# XOR_gate.net
KiCad netlist of a schematic drawn in EAGLE
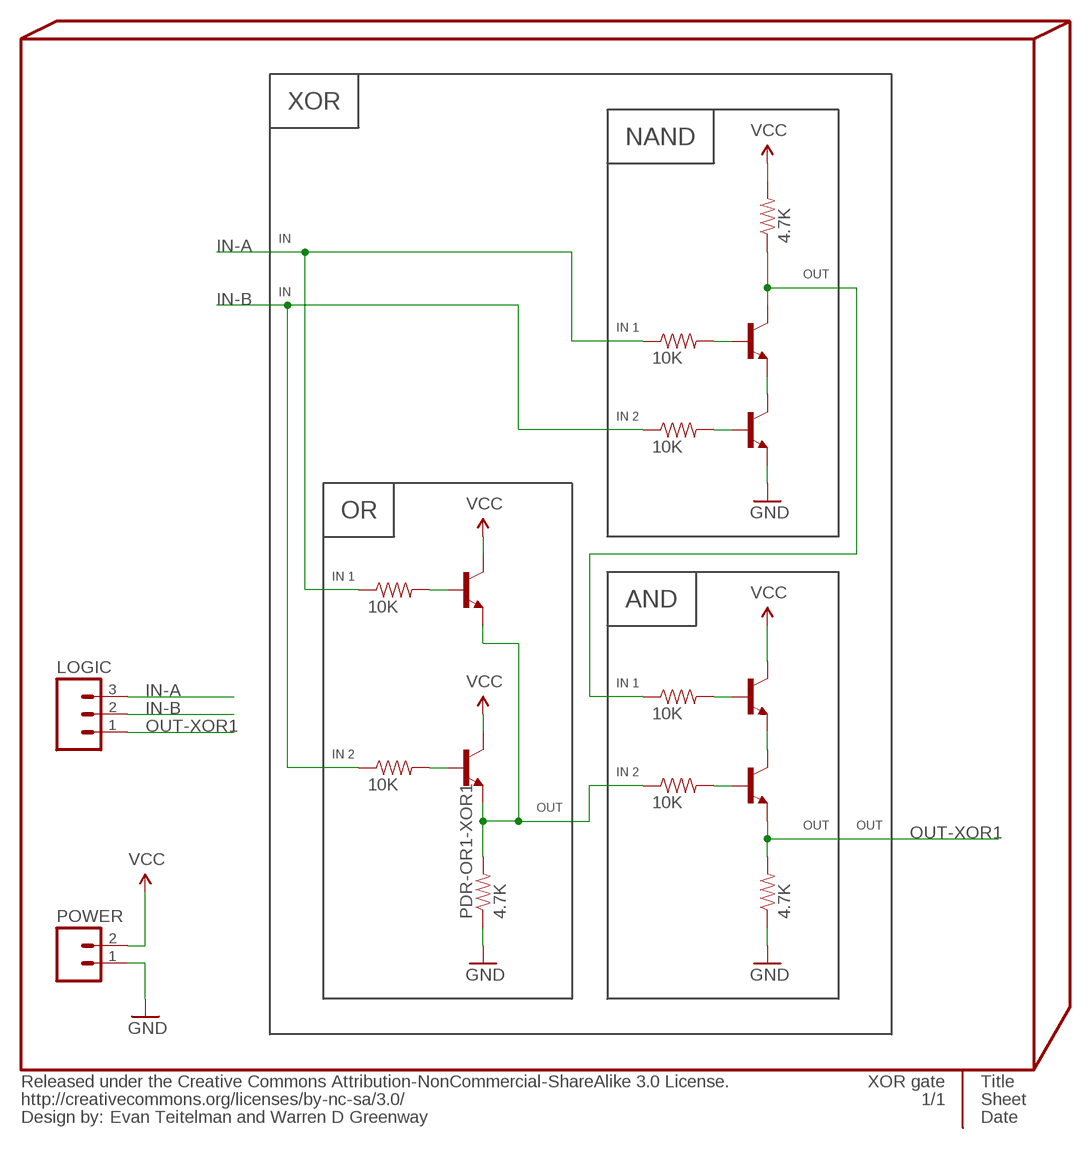
[diagram p0: schematic, sheet 1]

(export (version "E")
  (design (tool "Eeschema 10.0.6"))
  (components
    (comp (ref "INFO4")
      (value "Evan Teitelman and Warren D Greenway")
      (footprint "eagle-import:%CC-NC-SA")
      (libsource (lib "eagle-import") (part "%CC-NC-SA"))
    )
    (comp (ref "LOGIC")
      (value "M03PTH")
      (footprint "eagle-import:1X03")
      (libsource (lib "eagle-import") (part "M03PTH"))
    )
    (comp (ref "PDR-AND1-XOR1")
      (value "4.7K")
      (footprint "eagle-import:0402-RES")
      (libsource (lib "eagle-import") (part "RESISTOR0402-RES"))
    )
    (comp (ref "PDR-OR1-XOR1")
      (value "4.7K")
      (footprint "eagle-import:0402-RES")
      (libsource (lib "eagle-import") (part "RESISTOR0402-RES"))
    )
    (comp (ref "POWER")
      (value "M02PTH")
      (footprint "eagle-import:1X02")
      (libsource (lib "eagle-import") (part "M02PTH"))
    )
    (comp (ref "PUR-NAND1-XOR1")
      (value "4.7K")
      (footprint "eagle-import:0402-RES")
      (libsource (lib "eagle-import") (part "RESISTOR0402-RES"))
    )
    (comp (ref "Q1-AND1-XOR1")
      (value "TRANSISTOR_NPNSOT23")
      (footprint "eagle-import:SOT23")
      (libsource (lib "eagle-import") (part "TRANSISTOR_NPNSOT23"))
    )
    (comp (ref "Q1-NAND1-XOR1")
      (value "TRANSISTOR_NPNSOT23")
      (footprint "eagle-import:SOT23")
      (libsource (lib "eagle-import") (part "TRANSISTOR_NPNSOT23"))
    )
    (comp (ref "Q1-OR1-XOR1")
      (value "TRANSISTOR_NPNSOT23")
      (footprint "eagle-import:SOT23")
      (libsource (lib "eagle-import") (part "TRANSISTOR_NPNSOT23"))
    )
    (comp (ref "Q2-AND1-XOR1")
      (value "TRANSISTOR_NPNSOT23")
      (footprint "eagle-import:SOT23")
      (libsource (lib "eagle-import") (part "TRANSISTOR_NPNSOT23"))
    )
    (comp (ref "Q2-NAND1-XOR1")
      (value "TRANSISTOR_NPNSOT23")
      (footprint "eagle-import:SOT23")
      (libsource (lib "eagle-import") (part "TRANSISTOR_NPNSOT23"))
    )
    (comp (ref "Q2-OR1-XOR1")
      (value "TRANSISTOR_NPNSOT23")
      (footprint "eagle-import:SOT23")
      (libsource (lib "eagle-import") (part "TRANSISTOR_NPNSOT23"))
    )
    (comp (ref "R1-AND1-XOR1")
      (value "10K")
      (footprint "eagle-import:0402-RES")
      (libsource (lib "eagle-import") (part "RESISTOR0402-RES"))
    )
    (comp (ref "R1-NAND1-XOR1")
      (value "10K")
      (footprint "eagle-import:0402-RES")
      (libsource (lib "eagle-import") (part "RESISTOR0402-RES"))
    )
    (comp (ref "R1-OR1-XOR1")
      (value "10K")
      (footprint "eagle-import:0402-RES")
      (libsource (lib "eagle-import") (part "RESISTOR0402-RES"))
    )
    (comp (ref "R2-AND1-XOR1")
      (value "10K")
      (footprint "eagle-import:0402-RES")
      (libsource (lib "eagle-import") (part "RESISTOR0402-RES"))
    )
    (comp (ref "R2-NAND1-XOR1")
      (value "10K")
      (footprint "eagle-import:0402-RES")
      (libsource (lib "eagle-import") (part "RESISTOR0402-RES"))
    )
    (comp (ref "R2-OR1-XOR1")
      (value "10K")
      (footprint "eagle-import:0402-RES")
      (libsource (lib "eagle-import") (part "RESISTOR0402-RES"))
    )
  )
  (nets
    (net (code "1") (name "/IN-A") (class "Default")
      (node (ref "LOGIC") (pin "3") (pinfunction "3_3") (pintype "passive"))
      (node (ref "R1-NAND1-XOR1") (pin "1") (pinfunction "1_1") (pintype "passive"))
      (node (ref "R1-OR1-XOR1") (pin "1") (pinfunction "1_1") (pintype "passive"))
    )
    (net (code "2") (name "/IN-B") (class "Default")
      (node (ref "LOGIC") (pin "2") (pinfunction "2_2") (pintype "passive"))
      (node (ref "R2-NAND1-XOR1") (pin "1") (pinfunction "1_1") (pintype "passive"))
      (node (ref "R2-OR1-XOR1") (pin "1") (pinfunction "1_1") (pintype "passive"))
    )
    (net (code "3") (name "/OUT-XOR1") (class "Default")
      (node (ref "LOGIC") (pin "1") (pinfunction "1_1") (pintype "passive"))
      (node (ref "PDR-AND1-XOR1") (pin "2") (pinfunction "2_2") (pintype "passive"))
      (node (ref "Q2-AND1-XOR1") (pin "2") (pinfunction "E_2") (pintype "passive"))
    )
    (net (code "4") (name "@GND") (class "Default")
      (node (ref "PDR-AND1-XOR1") (pin "1") (pinfunction "1_1") (pintype "passive"))
      (node (ref "PDR-OR1-XOR1") (pin "1") (pinfunction "1_1") (pintype "passive"))
      (node (ref "POWER") (pin "1") (pinfunction "1_1") (pintype "passive"))
      (node (ref "Q2-NAND1-XOR1") (pin "2") (pinfunction "E_2") (pintype "passive"))
    )
    (net (code "5") (name "@VCC") (class "Default")
      (node (ref "POWER") (pin "2") (pinfunction "2_2") (pintype "passive"))
      (node (ref "PUR-NAND1-XOR1") (pin "2") (pinfunction "2_2") (pintype "passive"))
      (node (ref "Q1-AND1-XOR1") (pin "3") (pinfunction "C_3") (pintype "passive"))
      (node (ref "Q1-OR1-XOR1") (pin "3") (pinfunction "C_3") (pintype "passive"))
      (node (ref "Q2-OR1-XOR1") (pin "3") (pinfunction "C_3") (pintype "passive"))
    )
    (net (code "6") (name "Net-(Q1-AND1-XOR1-B)") (class "Default")
      (node (ref "Q1-AND1-XOR1") (pin "1") (pinfunction "B_1") (pintype "passive"))
      (node (ref "R1-AND1-XOR1") (pin "2") (pinfunction "2_2") (pintype "passive"))
    )
    (net (code "7") (name "Net-(Q1-AND1-XOR1-E)") (class "Default")
      (node (ref "Q1-AND1-XOR1") (pin "2") (pinfunction "E_2") (pintype "passive"))
      (node (ref "Q2-AND1-XOR1") (pin "3") (pinfunction "C_3") (pintype "passive"))
    )
    (net (code "8") (name "Net-(Q1-NAND1-XOR1-B)") (class "Default")
      (node (ref "Q1-NAND1-XOR1") (pin "1") (pinfunction "B_1") (pintype "passive"))
      (node (ref "R1-NAND1-XOR1") (pin "2") (pinfunction "2_2") (pintype "passive"))
    )
    (net (code "9") (name "Net-(Q1-NAND1-XOR1-C)") (class "Default")
      (node (ref "PUR-NAND1-XOR1") (pin "1") (pinfunction "1_1") (pintype "passive"))
      (node (ref "Q1-NAND1-XOR1") (pin "3") (pinfunction "C_3") (pintype "passive"))
      (node (ref "R1-AND1-XOR1") (pin "1") (pinfunction "1_1") (pintype "passive"))
    )
    (net (code "10") (name "Net-(Q1-NAND1-XOR1-E)") (class "Default")
      (node (ref "Q1-NAND1-XOR1") (pin "2") (pinfunction "E_2") (pintype "passive"))
      (node (ref "Q2-NAND1-XOR1") (pin "3") (pinfunction "C_3") (pintype "passive"))
    )
    (net (code "11") (name "Net-(Q1-OR1-XOR1-B)") (class "Default")
      (node (ref "Q1-OR1-XOR1") (pin "1") (pinfunction "B_1") (pintype "passive"))
      (node (ref "R1-OR1-XOR1") (pin "2") (pinfunction "2_2") (pintype "passive"))
    )
    (net (code "12") (name "Net-(Q1-OR1-XOR1-E)") (class "Default")
      (node (ref "PDR-OR1-XOR1") (pin "2") (pinfunction "2_2") (pintype "passive"))
      (node (ref "Q1-OR1-XOR1") (pin "2") (pinfunction "E_2") (pintype "passive"))
      (node (ref "Q2-OR1-XOR1") (pin "2") (pinfunction "E_2") (pintype "passive"))
      (node (ref "R2-AND1-XOR1") (pin "1") (pinfunction "1_1") (pintype "passive"))
    )
    (net (code "13") (name "Net-(Q2-AND1-XOR1-B)") (class "Default")
      (node (ref "Q2-AND1-XOR1") (pin "1") (pinfunction "B_1") (pintype "passive"))
      (node (ref "R2-AND1-XOR1") (pin "2") (pinfunction "2_2") (pintype "passive"))
    )
    (net (code "14") (name "Net-(Q2-NAND1-XOR1-B)") (class "Default")
      (node (ref "Q2-NAND1-XOR1") (pin "1") (pinfunction "B_1") (pintype "passive"))
      (node (ref "R2-NAND1-XOR1") (pin "2") (pinfunction "2_2") (pintype "passive"))
    )
    (net (code "15") (name "Net-(Q2-OR1-XOR1-B)") (class "Default")
      (node (ref "Q2-OR1-XOR1") (pin "1") (pinfunction "B_1") (pintype "passive"))
      (node (ref "R2-OR1-XOR1") (pin "2") (pinfunction "2_2") (pintype "passive"))
    )
  )
)
